# light_sensor.net
KiCad netlist of a schematic drawn in Altium Designer
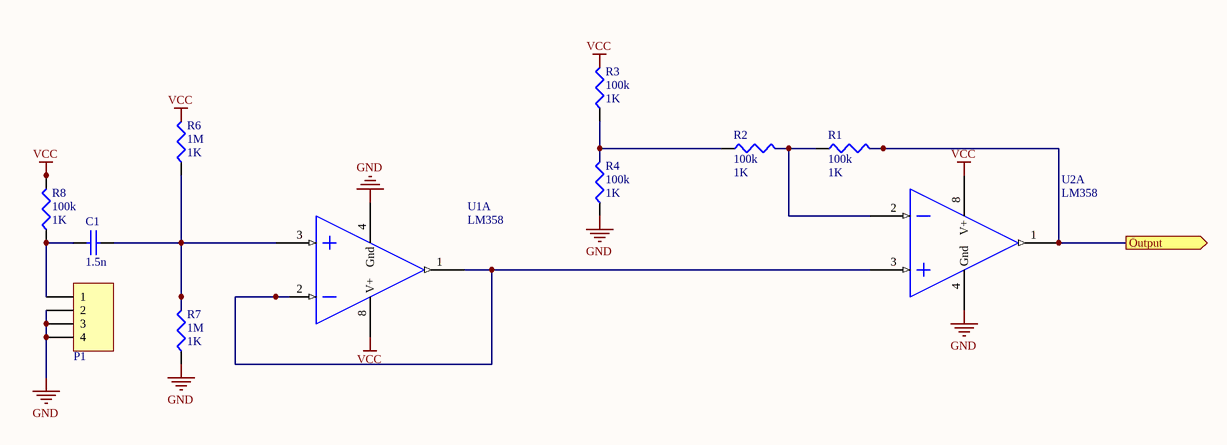
[diagram p0: light_sensor.SchDoc]

(export (version "E")
  (design (tool "Eeschema 10.0.6"))
  (components
    (comp (ref "C1")
      (value "1.5n")
      (footprint "ECE-CAPR0.2x0.1TH")
      (description "CAP CER 10pF 50V TH")
      (libsource (lib "EceParts") (part "Cap"))
    )
    (comp (ref "P1")
      (value "Phototransistor")
      (footprint "ECE-600104STTH")
      (description "HEADER POLARISED 4WAY TH")
      (libsource (lib "EceParts") (part "Header 4"))
    )
    (comp (ref "R1")
      (value "100k")
      (footprint "J1-0603")
      (description "Resistor")
      (fields (field (name "ALTIUM_VALUE") "1K") (field (name "PUBLISHER") "Altium Limited"))
      (libsource (lib "Miscellaneous Devices") (part "Res3"))
    )
    (comp (ref "R2")
      (value "100k")
      (footprint "J1-0603")
      (description "Resistor")
      (fields (field (name "ALTIUM_VALUE") "1K") (field (name "PUBLISHER") "Altium Limited"))
      (libsource (lib "Miscellaneous Devices") (part "Res3"))
    )
    (comp (ref "R3")
      (value "100k")
      (footprint "J1-0603")
      (description "Resistor")
      (fields (field (name "ALTIUM_VALUE") "1K") (field (name "PUBLISHER") "Altium Limited"))
      (libsource (lib "Miscellaneous Devices") (part "Res3"))
    )
    (comp (ref "R4")
      (value "100k")
      (footprint "J1-0603")
      (description "Resistor")
      (fields (field (name "ALTIUM_VALUE") "1K") (field (name "PUBLISHER") "Altium Limited"))
      (libsource (lib "Miscellaneous Devices") (part "Res3"))
    )
    (comp (ref "R6")
      (value "1M")
      (footprint "J1-0603")
      (description "Resistor")
      (fields (field (name "ALTIUM_VALUE") "1K") (field (name "PUBLISHER") "Altium Limited"))
      (libsource (lib "Miscellaneous Devices") (part "Res3"))
    )
    (comp (ref "R7")
      (value "1M")
      (footprint "J1-0603")
      (description "Resistor")
      (fields (field (name "ALTIUM_VALUE") "1K") (field (name "PUBLISHER") "Altium Limited"))
      (libsource (lib "Miscellaneous Devices") (part "Res3"))
    )
    (comp (ref "R8")
      (value "100k")
      (footprint "J1-0603")
      (description "Resistor")
      (fields (field (name "ALTIUM_VALUE") "1K") (field (name "PUBLISHER") "Altium Limited"))
      (libsource (lib "Miscellaneous Devices") (part "Res3"))
    )
    (comp (ref "U1")
      (value "LM358")
      (footprint "ECE-DIP8TH")
      (description "IC OPAMP LM358 DUAL TH")
      (libsource (lib "EceParts") (part "LM358"))
    )
    (comp (ref "U2")
      (value "LM358")
      (footprint "ECE-DIP8TH")
      (description "IC OPAMP LM358 DUAL TH")
      (libsource (lib "EceParts") (part "LM358"))
    )
  )
  (nets
    (net (code "1") (name "/Output") (class "Default")
      (node (ref "R1") (pin "2") (pinfunction "2_2") (pintype "passive"))
      (node (ref "U2") (pin "1") (pinfunction "OUT1_1") (pintype "output"))
    )
    (net (code "2") (name "GND") (class "Default")
      (node (ref "P1") (pin "2") (pinfunction "2_2") (pintype "passive"))
      (node (ref "P1") (pin "3") (pinfunction "3_3") (pintype "passive"))
      (node (ref "P1") (pin "4") (pinfunction "4_4") (pintype "passive"))
      (node (ref "R4") (pin "1") (pinfunction "1_1") (pintype "passive"))
      (node (ref "R7") (pin "1") (pinfunction "1_1") (pintype "passive"))
      (node (ref "U1") (pin "4") (pinfunction "Gnd_4") (pintype "power_in"))
      (node (ref "U2") (pin "4") (pinfunction "Gnd_4") (pintype "power_in"))
    )
    (net (code "3") (name "Net-(C1-Pad2)") (class "Default")
      (node (ref "C1") (pin "2") (pinfunction "2_2") (pintype "passive"))
      (node (ref "P1") (pin "1") (pinfunction "1_1") (pintype "passive"))
      (node (ref "R8") (pin "1") (pinfunction "1_1") (pintype "passive"))
    )
    (net (code "4") (name "Net-(R2-Pad1)") (class "Default")
      (node (ref "R2") (pin "1") (pinfunction "1_1") (pintype "passive"))
      (node (ref "R3") (pin "1") (pinfunction "1_1") (pintype "passive"))
      (node (ref "R4") (pin "2") (pinfunction "2_2") (pintype "passive"))
    )
    (net (code "5") (name "Net-(U1A-IN1(+))") (class "Default")
      (node (ref "C1") (pin "1") (pinfunction "1_1") (pintype "passive"))
      (node (ref "R6") (pin "1") (pinfunction "1_1") (pintype "passive"))
      (node (ref "R7") (pin "2") (pinfunction "2_2") (pintype "passive"))
      (node (ref "U1") (pin "3") (pinfunction "IN1(+)_3") (pintype "input"))
    )
    (net (code "6") (name "Net-(U1A-IN1(-))") (class "Default")
      (node (ref "U1") (pin "1") (pinfunction "OUT1_1") (pintype "output"))
      (node (ref "U1") (pin "2") (pinfunction "IN1(-)_2") (pintype "input"))
      (node (ref "U2") (pin "3") (pinfunction "IN1(+)_3") (pintype "input"))
    )
    (net (code "7") (name "Net-(U2A-IN1(-))") (class "Default")
      (node (ref "R1") (pin "1") (pinfunction "1_1") (pintype "passive"))
      (node (ref "R2") (pin "2") (pinfunction "2_2") (pintype "passive"))
      (node (ref "U2") (pin "2") (pinfunction "IN1(-)_2") (pintype "input"))
    )
    (net (code "8") (name "VCC") (class "Default")
      (node (ref "R8") (pin "2") (pinfunction "2_2") (pintype "passive"))
      (node (ref "U1") (pin "8") (pinfunction "V+_8") (pintype "power_in"))
      (node (ref "U2") (pin "8") (pinfunction "V+_8") (pintype "power_in"))
    )
    (net (code "9") (name "unconnected-(R3-Pad2)") (class "Default")
      (node (ref "R3") (pin "2") (pinfunction "2_2") (pintype "passive"))
    )
    (net (code "10") (name "unconnected-(R6-Pad2)") (class "Default")
      (node (ref "R6") (pin "2") (pinfunction "2_2") (pintype "passive"))
    )
  )
)
